# base-6u-custom-8535.net
KiCad netlist of a schematic drawn in EAGLE
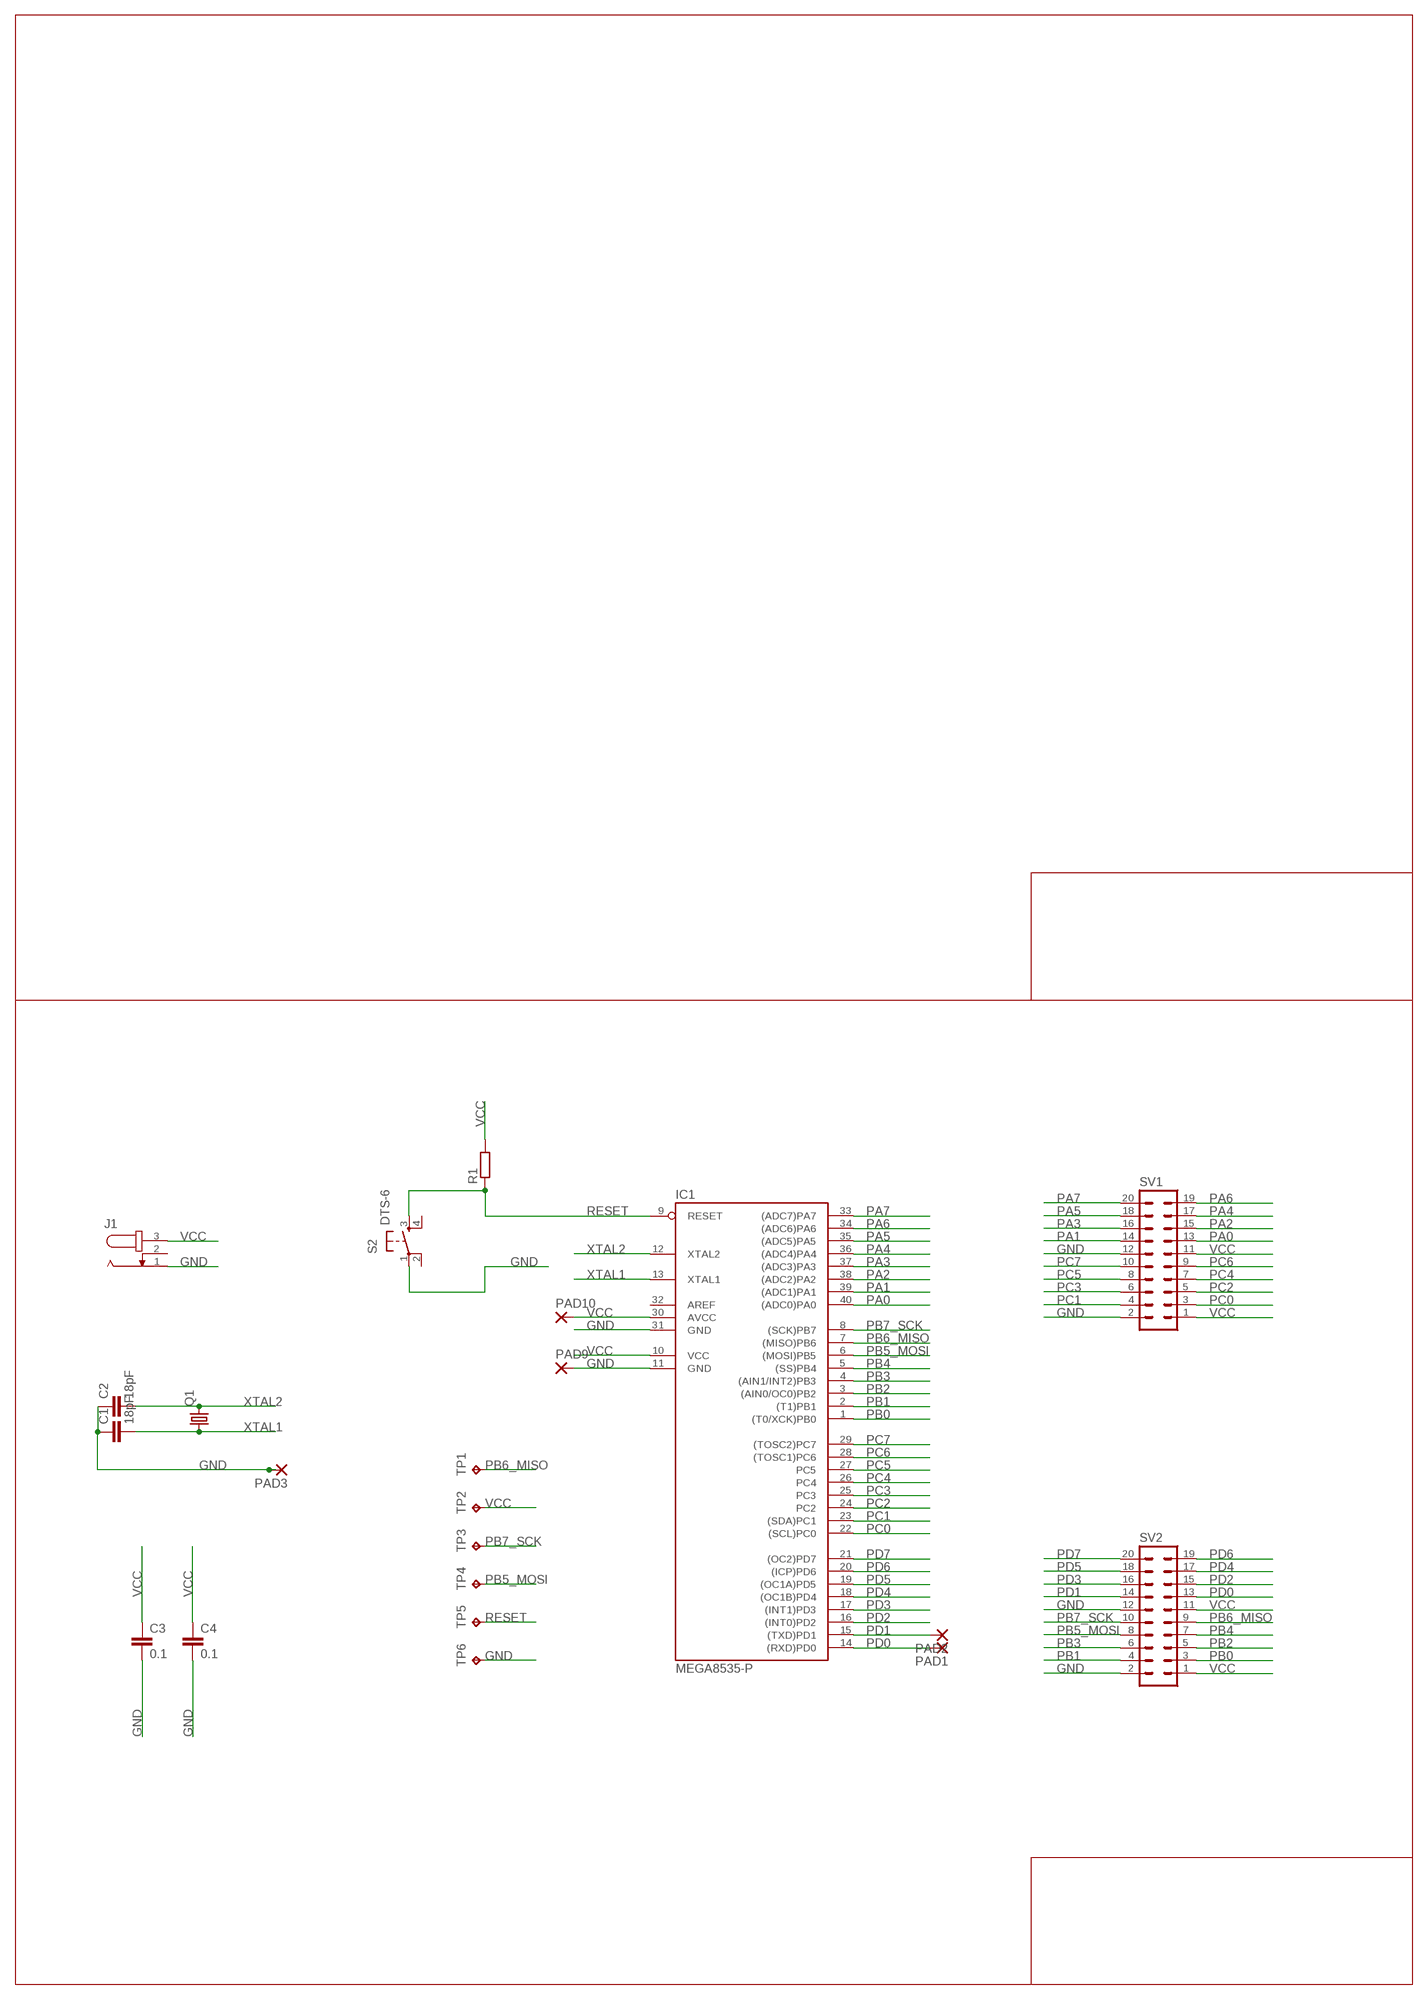
[diagram p0: schematic, sheet 1]

(export (version "E")
  (design (tool "Eeschema 10.0.6"))
  (components
    (comp (ref "C1")
      (value "18pF")
      (footprint "eagle-import:C0805")
      (libsource (lib "eagle-import") (part "C-EUC0805"))
    )
    (comp (ref "C2")
      (value "18pF")
      (footprint "eagle-import:C0805")
      (libsource (lib "eagle-import") (part "C-EUC0805"))
    )
    (comp (ref "C3")
      (value "0.1")
      (footprint "eagle-import:C0805")
      (libsource (lib "eagle-import") (part "C-EUC0805"))
    )
    (comp (ref "C4")
      (value "0.1")
      (footprint "eagle-import:C0805")
      (libsource (lib "eagle-import") (part "C-EUC0805"))
    )
    (comp (ref "IC1")
      (value "MEGA8535-P")
      (footprint "eagle-import:DIL40")
      (fields (field (name "MPN") "ATMEGA8535-16PU"))
      (libsource (lib "eagle-import") (part "MEGA8535-P"))
    )
    (comp (ref "J1")
      (value "JACK-PLUG1")
      (footprint "eagle-import:SPC4078")
      (libsource (lib "eagle-import") (part "JACK-PLUG1"))
    )
    (comp (ref "PAD1")
      (value "1,6/0,8")
      (footprint "eagle-import:1,6_0,8")
      (libsource (lib "eagle-import") (part "1,6/0,8"))
    )
    (comp (ref "PAD2")
      (value "1,6/0,8")
      (footprint "eagle-import:1,6_0,8")
      (libsource (lib "eagle-import") (part "1,6/0,8"))
    )
    (comp (ref "PAD3")
      (value "1,6/0,8")
      (footprint "eagle-import:1,6_0,8")
      (libsource (lib "eagle-import") (part "1,6/0,8"))
    )
    (comp (ref "PAD9")
      (value "1,6/0,8")
      (footprint "eagle-import:1,6_0,8")
      (libsource (lib "eagle-import") (part "1,6/0,8"))
    )
    (comp (ref "PAD10")
      (value "1,6/0,8")
      (footprint "eagle-import:1,6_0,8")
      (libsource (lib "eagle-import") (part "1,6/0,8"))
    )
    (comp (ref "Q1")
      (value "CRYSTALHC49S")
      (footprint "eagle-import:HC49_S")
      (libsource (lib "eagle-import") (part "CRYSTALHC49S"))
    )
    (comp (ref "R1")
      (value "R-EU_0204/2V")
      (footprint "eagle-import:0204V")
      (libsource (lib "eagle-import") (part "R-EU_0204/2V"))
    )
    (comp (ref "S2")
      (value "DTS-6")
      (footprint "eagle-import:DTS-6")
      (libsource (lib "eagle-import") (part "DTS-6"))
    )
    (comp (ref "SV1")
      (value "MA10-2")
      (footprint "eagle-import:MA10-2")
      (libsource (lib "eagle-import") (part "MA10-2"))
    )
    (comp (ref "SV2")
      (value "MA10-2")
      (footprint "eagle-import:MA10-2")
      (libsource (lib "eagle-import") (part "MA10-2"))
    )
    (comp (ref "TP1")
      (value "TPTP16R")
      (footprint "eagle-import:TP16R")
      (libsource (lib "eagle-import") (part "TPTP16R"))
    )
    (comp (ref "TP2")
      (value "TPTP16R")
      (footprint "eagle-import:TP16R")
      (libsource (lib "eagle-import") (part "TPTP16R"))
    )
    (comp (ref "TP3")
      (value "TPTP16R")
      (footprint "eagle-import:TP16R")
      (libsource (lib "eagle-import") (part "TPTP16R"))
    )
    (comp (ref "TP4")
      (value "TPTP16R")
      (footprint "eagle-import:TP16R")
      (libsource (lib "eagle-import") (part "TPTP16R"))
    )
    (comp (ref "TP5")
      (value "TPTP16R")
      (footprint "eagle-import:TP16R")
      (libsource (lib "eagle-import") (part "TPTP16R"))
    )
    (comp (ref "TP6")
      (value "TPTP16R")
      (footprint "eagle-import:TP16R")
      (libsource (lib "eagle-import") (part "TPTP16R"))
    )
  )
  (nets
    (net (code "1") (name "/GND") (class "Default")
      (node (ref "C1") (pin "1") (pinfunction "1_1") (pintype "passive"))
      (node (ref "C2") (pin "1") (pinfunction "1_1") (pintype "passive"))
      (node (ref "C3") (pin "2") (pinfunction "2_2") (pintype "passive"))
      (node (ref "C4") (pin "2") (pinfunction "2_2") (pintype "passive"))
      (node (ref "IC1") (pin "11") (pinfunction "GND_11") (pintype "power_in"))
      (node (ref "IC1") (pin "31") (pinfunction "GND_31") (pintype "power_in"))
      (node (ref "J1") (pin "1") (pinfunction "1_1") (pintype "passive"))
      (node (ref "PAD3") (pin "1") (pinfunction "P_1") (pintype "passive"))
      (node (ref "PAD9") (pin "1") (pinfunction "P_1") (pintype "passive"))
      (node (ref "S2") (pin "1") (pinfunction "1_1") (pintype "passive"))
      (node (ref "SV1") (pin "12") (pinfunction "12_12") (pintype "passive"))
      (node (ref "SV1") (pin "2") (pinfunction "2_2") (pintype "passive"))
      (node (ref "SV2") (pin "12") (pinfunction "12_12") (pintype "passive"))
      (node (ref "SV2") (pin "2") (pinfunction "2_2") (pintype "passive"))
      (node (ref "TP6") (pin "TP") (pinfunction "TP_TP") (pintype "input"))
    )
    (net (code "2") (name "/PA0") (class "Default")
      (node (ref "IC1") (pin "40") (pinfunction "(ADC0)PA0_40") (pintype "bidirectional"))
      (node (ref "SV1") (pin "13") (pinfunction "13_13") (pintype "passive"))
    )
    (net (code "3") (name "/PA1") (class "Default")
      (node (ref "IC1") (pin "39") (pinfunction "(ADC1)PA1_39") (pintype "bidirectional"))
      (node (ref "SV1") (pin "14") (pinfunction "14_14") (pintype "passive"))
    )
    (net (code "4") (name "/PA2") (class "Default")
      (node (ref "IC1") (pin "38") (pinfunction "(ADC2)PA2_38") (pintype "bidirectional"))
      (node (ref "SV1") (pin "15") (pinfunction "15_15") (pintype "passive"))
    )
    (net (code "5") (name "/PA3") (class "Default")
      (node (ref "IC1") (pin "37") (pinfunction "(ADC3)PA3_37") (pintype "bidirectional"))
      (node (ref "SV1") (pin "16") (pinfunction "16_16") (pintype "passive"))
    )
    (net (code "6") (name "/PA4") (class "Default")
      (node (ref "IC1") (pin "36") (pinfunction "(ADC4)PA4_36") (pintype "bidirectional"))
      (node (ref "SV1") (pin "17") (pinfunction "17_17") (pintype "passive"))
    )
    (net (code "7") (name "/PA5") (class "Default")
      (node (ref "IC1") (pin "35") (pinfunction "(ADC5)PA5_35") (pintype "bidirectional"))
      (node (ref "SV1") (pin "18") (pinfunction "18_18") (pintype "passive"))
    )
    (net (code "8") (name "/PA6") (class "Default")
      (node (ref "IC1") (pin "34") (pinfunction "(ADC6)PA6_34") (pintype "bidirectional"))
      (node (ref "SV1") (pin "19") (pinfunction "19_19") (pintype "passive"))
    )
    (net (code "9") (name "/PA7") (class "Default")
      (node (ref "IC1") (pin "33") (pinfunction "(ADC7)PA7_33") (pintype "bidirectional"))
      (node (ref "SV1") (pin "20") (pinfunction "20_20") (pintype "passive"))
    )
    (net (code "10") (name "/PB0") (class "Default")
      (node (ref "IC1") (pin "1") (pinfunction "(T0/XCK)PB0_1") (pintype "bidirectional"))
      (node (ref "SV2") (pin "3") (pinfunction "3_3") (pintype "passive"))
    )
    (net (code "11") (name "/PB1") (class "Default")
      (node (ref "IC1") (pin "2") (pinfunction "(T1)PB1_2") (pintype "bidirectional"))
      (node (ref "SV2") (pin "4") (pinfunction "4_4") (pintype "passive"))
    )
    (net (code "12") (name "/PB2") (class "Default")
      (node (ref "IC1") (pin "3") (pinfunction "(AIN0/OC0)PB2_3") (pintype "bidirectional"))
      (node (ref "SV2") (pin "5") (pinfunction "5_5") (pintype "passive"))
    )
    (net (code "13") (name "/PB3") (class "Default")
      (node (ref "IC1") (pin "4") (pinfunction "(AIN1/INT2)PB3_4") (pintype "bidirectional"))
      (node (ref "SV2") (pin "6") (pinfunction "6_6") (pintype "passive"))
    )
    (net (code "14") (name "/PB4") (class "Default")
      (node (ref "IC1") (pin "5") (pinfunction "(SS)PB4_5") (pintype "bidirectional"))
      (node (ref "SV2") (pin "7") (pinfunction "7_7") (pintype "passive"))
    )
    (net (code "15") (name "/PB5_MOSI") (class "Default")
      (node (ref "IC1") (pin "6") (pinfunction "(MOSI)PB5_6") (pintype "bidirectional"))
      (node (ref "SV2") (pin "8") (pinfunction "8_8") (pintype "passive"))
      (node (ref "TP4") (pin "TP") (pinfunction "TP_TP") (pintype "input"))
    )
    (net (code "16") (name "/PB6_MISO") (class "Default")
      (node (ref "IC1") (pin "7") (pinfunction "(MISO)PB6_7") (pintype "bidirectional"))
      (node (ref "SV2") (pin "9") (pinfunction "9_9") (pintype "passive"))
      (node (ref "TP1") (pin "TP") (pinfunction "TP_TP") (pintype "input"))
    )
    (net (code "17") (name "/PB7_SCK") (class "Default")
      (node (ref "IC1") (pin "8") (pinfunction "(SCK)PB7_8") (pintype "bidirectional"))
      (node (ref "SV2") (pin "10") (pinfunction "10_10") (pintype "passive"))
      (node (ref "TP3") (pin "TP") (pinfunction "TP_TP") (pintype "input"))
    )
    (net (code "18") (name "/PC0") (class "Default")
      (node (ref "IC1") (pin "22") (pinfunction "(SCL)PC0_22") (pintype "bidirectional"))
      (node (ref "SV1") (pin "3") (pinfunction "3_3") (pintype "passive"))
    )
    (net (code "19") (name "/PC1") (class "Default")
      (node (ref "IC1") (pin "23") (pinfunction "(SDA)PC1_23") (pintype "bidirectional"))
      (node (ref "SV1") (pin "4") (pinfunction "4_4") (pintype "passive"))
    )
    (net (code "20") (name "/PC2") (class "Default")
      (node (ref "IC1") (pin "24") (pinfunction "PC2_24") (pintype "bidirectional"))
      (node (ref "SV1") (pin "5") (pinfunction "5_5") (pintype "passive"))
    )
    (net (code "21") (name "/PC3") (class "Default")
      (node (ref "IC1") (pin "25") (pinfunction "PC3_25") (pintype "bidirectional"))
      (node (ref "SV1") (pin "6") (pinfunction "6_6") (pintype "passive"))
    )
    (net (code "22") (name "/PC4") (class "Default")
      (node (ref "IC1") (pin "26") (pinfunction "PC4_26") (pintype "bidirectional"))
      (node (ref "SV1") (pin "7") (pinfunction "7_7") (pintype "passive"))
    )
    (net (code "23") (name "/PC5") (class "Default")
      (node (ref "IC1") (pin "27") (pinfunction "PC5_27") (pintype "bidirectional"))
      (node (ref "SV1") (pin "8") (pinfunction "8_8") (pintype "passive"))
    )
    (net (code "24") (name "/PC6") (class "Default")
      (node (ref "IC1") (pin "28") (pinfunction "(TOSC1)PC6_28") (pintype "bidirectional"))
      (node (ref "SV1") (pin "9") (pinfunction "9_9") (pintype "passive"))
    )
    (net (code "25") (name "/PC7") (class "Default")
      (node (ref "IC1") (pin "29") (pinfunction "(TOSC2)PC7_29") (pintype "bidirectional"))
      (node (ref "SV1") (pin "10") (pinfunction "10_10") (pintype "passive"))
    )
    (net (code "26") (name "/PD0") (class "Default")
      (node (ref "IC1") (pin "14") (pinfunction "(RXD)PD0_14") (pintype "bidirectional"))
      (node (ref "PAD1") (pin "1") (pinfunction "P_1") (pintype "passive"))
      (node (ref "SV2") (pin "13") (pinfunction "13_13") (pintype "passive"))
    )
    (net (code "27") (name "/PD1") (class "Default")
      (node (ref "IC1") (pin "15") (pinfunction "(TXD)PD1_15") (pintype "bidirectional"))
      (node (ref "PAD2") (pin "1") (pinfunction "P_1") (pintype "passive"))
      (node (ref "SV2") (pin "14") (pinfunction "14_14") (pintype "passive"))
    )
    (net (code "28") (name "/PD2") (class "Default")
      (node (ref "IC1") (pin "16") (pinfunction "(INT0)PD2_16") (pintype "bidirectional"))
      (node (ref "SV2") (pin "15") (pinfunction "15_15") (pintype "passive"))
    )
    (net (code "29") (name "/PD3") (class "Default")
      (node (ref "IC1") (pin "17") (pinfunction "(INT1)PD3_17") (pintype "bidirectional"))
      (node (ref "SV2") (pin "16") (pinfunction "16_16") (pintype "passive"))
    )
    (net (code "30") (name "/PD4") (class "Default")
      (node (ref "IC1") (pin "18") (pinfunction "(OC1B)PD4_18") (pintype "bidirectional"))
      (node (ref "SV2") (pin "17") (pinfunction "17_17") (pintype "passive"))
    )
    (net (code "31") (name "/PD5") (class "Default")
      (node (ref "IC1") (pin "19") (pinfunction "(OC1A)PD5_19") (pintype "bidirectional"))
      (node (ref "SV2") (pin "18") (pinfunction "18_18") (pintype "passive"))
    )
    (net (code "32") (name "/PD6") (class "Default")
      (node (ref "IC1") (pin "20") (pinfunction "(ICP)PD6_20") (pintype "bidirectional"))
      (node (ref "SV2") (pin "19") (pinfunction "19_19") (pintype "passive"))
    )
    (net (code "33") (name "/PD7") (class "Default")
      (node (ref "IC1") (pin "21") (pinfunction "(OC2)PD7_21") (pintype "bidirectional"))
      (node (ref "SV2") (pin "20") (pinfunction "20_20") (pintype "passive"))
    )
    (net (code "34") (name "/RESET") (class "Default")
      (node (ref "IC1") (pin "9") (pinfunction "RESET_9") (pintype "input"))
      (node (ref "R1") (pin "1") (pinfunction "1_1") (pintype "passive"))
      (node (ref "S2") (pin "3") (pinfunction "3_3") (pintype "passive"))
      (node (ref "TP5") (pin "TP") (pinfunction "TP_TP") (pintype "input"))
    )
    (net (code "35") (name "/VCC") (class "Default")
      (node (ref "C3") (pin "1") (pinfunction "1_1") (pintype "passive"))
      (node (ref "C4") (pin "1") (pinfunction "1_1") (pintype "passive"))
      (node (ref "IC1") (pin "10") (pinfunction "VCC_10") (pintype "power_in"))
      (node (ref "IC1") (pin "30") (pinfunction "AVCC_30") (pintype "power_in"))
      (node (ref "J1") (pin "3") (pinfunction "3_3") (pintype "passive"))
      (node (ref "PAD10") (pin "1") (pinfunction "P_1") (pintype "passive"))
      (node (ref "R1") (pin "2") (pinfunction "2_2") (pintype "passive"))
      (node (ref "SV1") (pin "1") (pinfunction "1_1") (pintype "passive"))
      (node (ref "SV1") (pin "11") (pinfunction "11_11") (pintype "passive"))
      (node (ref "SV2") (pin "1") (pinfunction "1_1") (pintype "passive"))
      (node (ref "SV2") (pin "11") (pinfunction "11_11") (pintype "passive"))
      (node (ref "TP2") (pin "TP") (pinfunction "TP_TP") (pintype "input"))
    )
    (net (code "36") (name "/XTAL1") (class "Default")
      (node (ref "C1") (pin "2") (pinfunction "2_2") (pintype "passive"))
      (node (ref "IC1") (pin "13") (pinfunction "XTAL1_13") (pintype "bidirectional"))
      (node (ref "Q1") (pin "1") (pinfunction "1_1") (pintype "passive"))
    )
    (net (code "37") (name "/XTAL2") (class "Default")
      (node (ref "C2") (pin "2") (pinfunction "2_2") (pintype "passive"))
      (node (ref "IC1") (pin "12") (pinfunction "XTAL2_12") (pintype "bidirectional"))
      (node (ref "Q1") (pin "2") (pinfunction "2_2") (pintype "passive"))
    )
    (net (code "38") (name "unconnected-(IC1-AREF-Pad32)") (class "Default")
      (node (ref "IC1") (pin "32") (pinfunction "AREF_32") (pintype "passive"))
    )
    (net (code "39") (name "unconnected-(J1-Pad2)") (class "Default")
      (node (ref "J1") (pin "2") (pinfunction "2_2") (pintype "passive"))
    )
    (net (code "40") (name "unconnected-(S2-Pad2)") (class "Default")
      (node (ref "S2") (pin "2") (pinfunction "2_2") (pintype "passive"))
    )
    (net (code "41") (name "unconnected-(S2-Pad4)") (class "Default")
      (node (ref "S2") (pin "4") (pinfunction "4_4") (pintype "passive"))
    )
  )
)
